# AK4493-v1_64_10.net
KiCad netlist of a schematic drawn in EAGLE
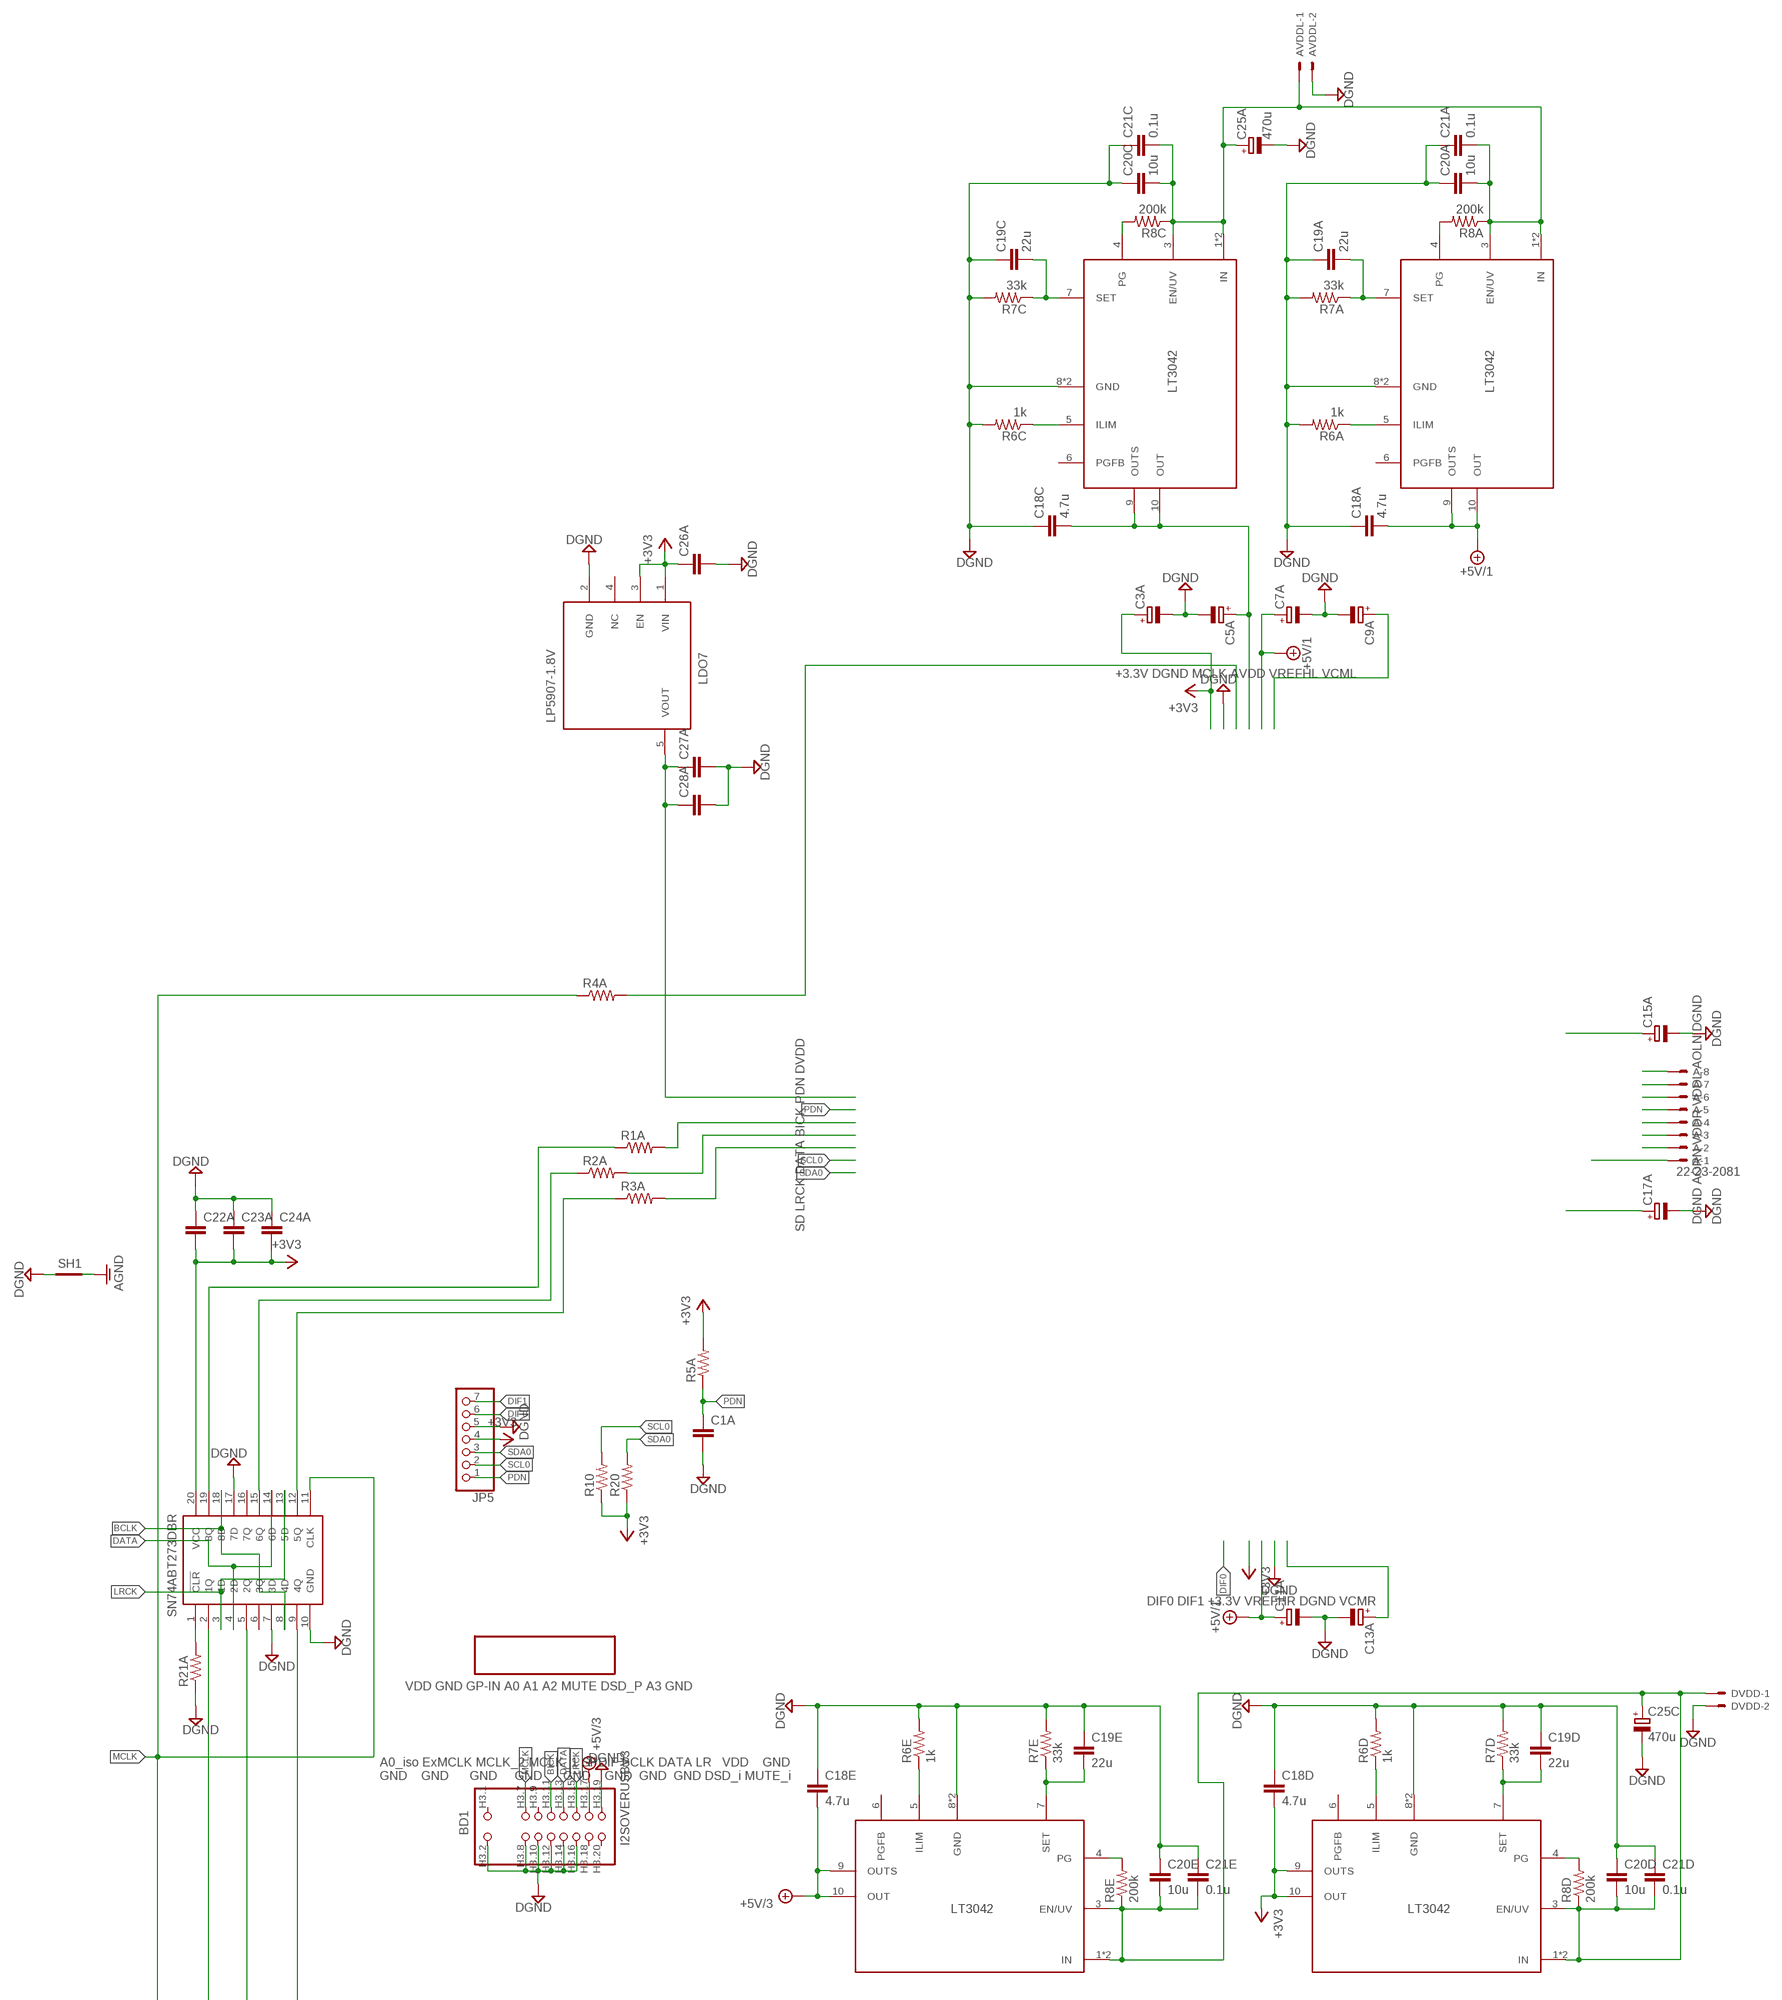
[diagram p0: schematic, sheet 1, part 1 of 2]
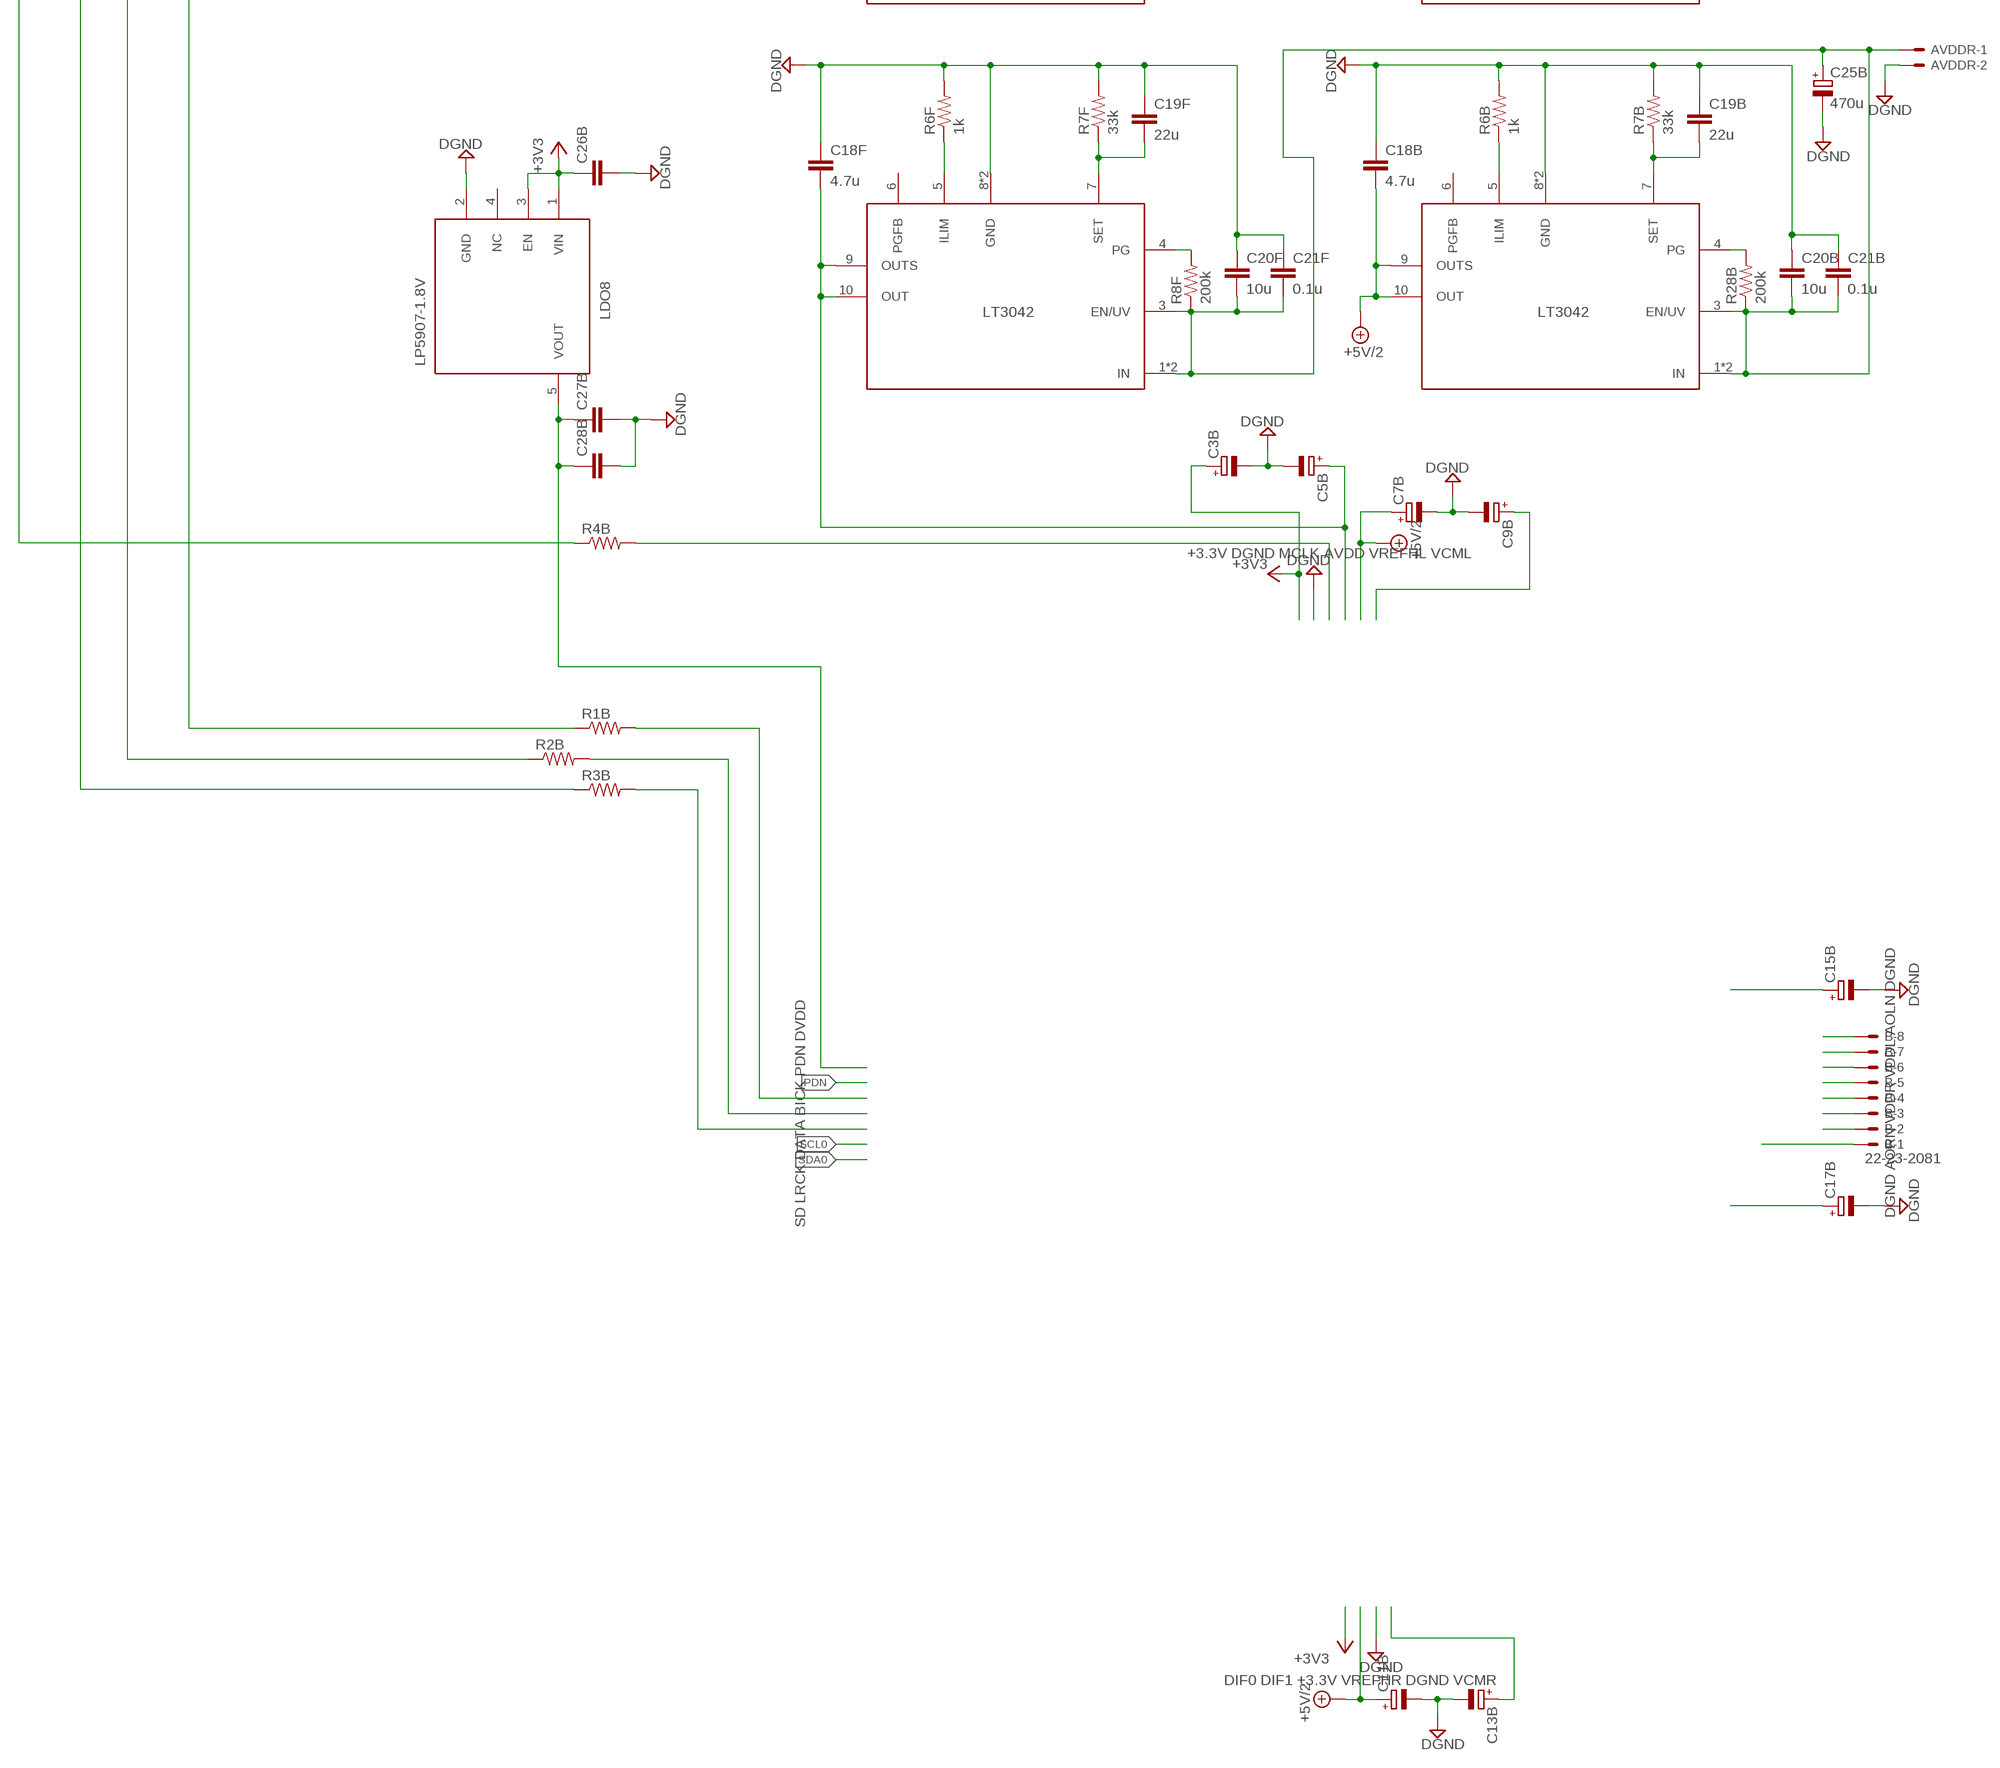
[diagram p1: schematic, sheet 1, part 2 of 2]

(export (version "E")
  (design (tool "Eeschema 10.0.6"))
  (components
    (comp (ref "A")
      (value "22-23-2081")
      (footprint "eagle-import:22-23-2081")
      (fields (field (name "MF") "MOLEX"))
      (libsource (lib "eagle-import") (part "22-23-2081"))
    )
    (comp (ref "AVDDL")
      (value "22-23-2021")
      (footprint "eagle-import:22-23-2021")
      (fields (field (name "MF") "MOLEX"))
      (libsource (lib "eagle-import") (part "22-23-2021"))
    )
    (comp (ref "AVDDR")
      (value "22-23-2021")
      (footprint "eagle-import:22-23-2021")
      (fields (field (name "MF") "MOLEX"))
      (libsource (lib "eagle-import") (part "22-23-2021"))
    )
    (comp (ref "B")
      (value "22-23-2081")
      (footprint "eagle-import:22-23-2081")
      (fields (field (name "MF") "MOLEX"))
      (libsource (lib "eagle-import") (part "22-23-2081"))
    )
    (comp (ref "BD1")
      (value "I2SOVERUSBV3")
      (footprint "eagle-import:I2SOVERUSBV3")
      (libsource (lib "eagle-import") (part "I2SOVERUSBV3"))
    )
    (comp (ref "C1A")
      (value "C-EUC0805K")
      (footprint "eagle-import:C0805K")
      (libsource (lib "eagle-import") (part "C-EUC0805K"))
    )
    (comp (ref "C3A")
      (value "CPOL-EUE2.5-5")
      (footprint "eagle-import:E2,5-5")
      (libsource (lib "eagle-import") (part "CPOL-EUE2.5-5"))
    )
    (comp (ref "C3B")
      (value "CPOL-EUE2.5-5")
      (footprint "eagle-import:E2,5-5")
      (libsource (lib "eagle-import") (part "CPOL-EUE2.5-5"))
    )
    (comp (ref "C5A")
      (value "CPOL-EUE2.5-5")
      (footprint "eagle-import:E2,5-5")
      (libsource (lib "eagle-import") (part "CPOL-EUE2.5-5"))
    )
    (comp (ref "C5B")
      (value "CPOL-EUE2.5-5")
      (footprint "eagle-import:E2,5-5")
      (libsource (lib "eagle-import") (part "CPOL-EUE2.5-5"))
    )
    (comp (ref "C7A")
      (value "CPOL-EUE5-8.5")
      (footprint "eagle-import:E5-8,5")
      (libsource (lib "eagle-import") (part "CPOL-EUE5-8.5"))
    )
    (comp (ref "C7B")
      (value "CPOL-EUE5-8.5")
      (footprint "eagle-import:E5-8,5")
      (libsource (lib "eagle-import") (part "CPOL-EUE5-8.5"))
    )
    (comp (ref "C9A")
      (value "CPOL-EUE2-4")
      (footprint "eagle-import:E2-4")
      (libsource (lib "eagle-import") (part "CPOL-EUE2-4"))
    )
    (comp (ref "C9B")
      (value "CPOL-EUE2-4")
      (footprint "eagle-import:E2-4")
      (libsource (lib "eagle-import") (part "CPOL-EUE2-4"))
    )
    (comp (ref "C11A")
      (value "CPOL-EUE5-8.5")
      (footprint "eagle-import:E5-8,5")
      (libsource (lib "eagle-import") (part "CPOL-EUE5-8.5"))
    )
    (comp (ref "C11B")
      (value "CPOL-EUE5-8.5")
      (footprint "eagle-import:E5-8,5")
      (libsource (lib "eagle-import") (part "CPOL-EUE5-8.5"))
    )
    (comp (ref "C13A")
      (value "CPOL-EUE2-4")
      (footprint "eagle-import:E2-4")
      (libsource (lib "eagle-import") (part "CPOL-EUE2-4"))
    )
    (comp (ref "C13B")
      (value "CPOL-EUE2-4")
      (footprint "eagle-import:E2-4")
      (libsource (lib "eagle-import") (part "CPOL-EUE2-4"))
    )
    (comp (ref "C15A")
      (value "CPOL-EUE2-4")
      (footprint "eagle-import:E2-4")
      (libsource (lib "eagle-import") (part "CPOL-EUE2-4"))
    )
    (comp (ref "C15B")
      (value "CPOL-EUE2-4")
      (footprint "eagle-import:E2-4")
      (libsource (lib "eagle-import") (part "CPOL-EUE2-4"))
    )
    (comp (ref "C17A")
      (value "CPOL-EUE2-4")
      (footprint "eagle-import:E2-4")
      (libsource (lib "eagle-import") (part "CPOL-EUE2-4"))
    )
    (comp (ref "C17B")
      (value "CPOL-EUE2-4")
      (footprint "eagle-import:E2-4")
      (libsource (lib "eagle-import") (part "CPOL-EUE2-4"))
    )
    (comp (ref "C18A")
      (value "4.7u")
      (footprint "eagle-import:C0805K")
      (libsource (lib "eagle-import") (part "C-EUC0805K"))
    )
    (comp (ref "C18B")
      (value "4.7u")
      (footprint "eagle-import:C0805K")
      (libsource (lib "eagle-import") (part "C-EUC0805K"))
    )
    (comp (ref "C18C")
      (value "4.7u")
      (footprint "eagle-import:C0805K")
      (libsource (lib "eagle-import") (part "C-EUC0805K"))
    )
    (comp (ref "C18D")
      (value "4.7u")
      (footprint "eagle-import:C0805K")
      (libsource (lib "eagle-import") (part "C-EUC0805K"))
    )
    (comp (ref "C18E")
      (value "4.7u")
      (footprint "eagle-import:C0805K")
      (libsource (lib "eagle-import") (part "C-EUC0805K"))
    )
    (comp (ref "C18F")
      (value "4.7u")
      (footprint "eagle-import:C0805K")
      (libsource (lib "eagle-import") (part "C-EUC0805K"))
    )
    (comp (ref "C19A")
      (value "22u")
      (footprint "eagle-import:C1206K")
      (libsource (lib "eagle-import") (part "C-EUC1206K"))
    )
    (comp (ref "C19B")
      (value "22u")
      (footprint "eagle-import:C1206K")
      (libsource (lib "eagle-import") (part "C-EUC1206K"))
    )
    (comp (ref "C19C")
      (value "22u")
      (footprint "eagle-import:C1206K")
      (libsource (lib "eagle-import") (part "C-EUC1206K"))
    )
    (comp (ref "C19D")
      (value "22u")
      (footprint "eagle-import:C1206K")
      (libsource (lib "eagle-import") (part "C-EUC1206K"))
    )
    (comp (ref "C19E")
      (value "22u")
      (footprint "eagle-import:C1206K")
      (libsource (lib "eagle-import") (part "C-EUC1206K"))
    )
    (comp (ref "C19F")
      (value "22u")
      (footprint "eagle-import:C1206K")
      (libsource (lib "eagle-import") (part "C-EUC1206K"))
    )
    (comp (ref "C20A")
      (value "10u")
      (footprint "eagle-import:C0805K")
      (libsource (lib "eagle-import") (part "C-EUC0805K"))
    )
    (comp (ref "C20B")
      (value "10u")
      (footprint "eagle-import:C0805K")
      (libsource (lib "eagle-import") (part "C-EUC0805K"))
    )
    (comp (ref "C20C")
      (value "10u")
      (footprint "eagle-import:C0805K")
      (libsource (lib "eagle-import") (part "C-EUC0805K"))
    )
    (comp (ref "C20D")
      (value "10u")
      (footprint "eagle-import:C0805K")
      (libsource (lib "eagle-import") (part "C-EUC0805K"))
    )
    (comp (ref "C20E")
      (value "10u")
      (footprint "eagle-import:C0805K")
      (libsource (lib "eagle-import") (part "C-EUC0805K"))
    )
    (comp (ref "C20F")
      (value "10u")
      (footprint "eagle-import:C0805K")
      (libsource (lib "eagle-import") (part "C-EUC0805K"))
    )
    (comp (ref "C21A")
      (value "0.1u")
      (footprint "eagle-import:C0805K")
      (libsource (lib "eagle-import") (part "C-EUC0805K"))
    )
    (comp (ref "C21B")
      (value "0.1u")
      (footprint "eagle-import:C0805K")
      (libsource (lib "eagle-import") (part "C-EUC0805K"))
    )
    (comp (ref "C21C")
      (value "0.1u")
      (footprint "eagle-import:C0805K")
      (libsource (lib "eagle-import") (part "C-EUC0805K"))
    )
    (comp (ref "C21D")
      (value "0.1u")
      (footprint "eagle-import:C0805K")
      (libsource (lib "eagle-import") (part "C-EUC0805K"))
    )
    (comp (ref "C21E")
      (value "0.1u")
      (footprint "eagle-import:C0805K")
      (libsource (lib "eagle-import") (part "C-EUC0805K"))
    )
    (comp (ref "C21F")
      (value "0.1u")
      (footprint "eagle-import:C0805K")
      (libsource (lib "eagle-import") (part "C-EUC0805K"))
    )
    (comp (ref "C22A")
      (value "C-EUC0603K")
      (footprint "eagle-import:C0603K")
      (libsource (lib "eagle-import") (part "C-EUC0603K"))
    )
    (comp (ref "C23A")
      (value "C-EUC0603K")
      (footprint "eagle-import:C0603K")
      (libsource (lib "eagle-import") (part "C-EUC0603K"))
    )
    (comp (ref "C24A")
      (value "C-EUC0603K")
      (footprint "eagle-import:C0603K")
      (libsource (lib "eagle-import") (part "C-EUC0603K"))
    )
    (comp (ref "C25A")
      (value "470u")
      (footprint "eagle-import:E2,5-7")
      (libsource (lib "eagle-import") (part "CPOL-EUE2.5-7"))
    )
    (comp (ref "C25B")
      (value "470u")
      (footprint "eagle-import:E2,5-7")
      (libsource (lib "eagle-import") (part "CPOL-EUE2.5-7"))
    )
    (comp (ref "C25C")
      (value "470u")
      (footprint "eagle-import:E2,5-7")
      (libsource (lib "eagle-import") (part "CPOL-EUE2.5-7"))
    )
    (comp (ref "C26A")
      (value "C-EUC0805K")
      (footprint "eagle-import:C0805K")
      (libsource (lib "eagle-import") (part "C-EUC0805K"))
    )
    (comp (ref "C26B")
      (value "C-EUC0805K")
      (footprint "eagle-import:C0805K")
      (libsource (lib "eagle-import") (part "C-EUC0805K"))
    )
    (comp (ref "C27A")
      (value "C-EUC0805K")
      (footprint "eagle-import:C0805K")
      (libsource (lib "eagle-import") (part "C-EUC0805K"))
    )
    (comp (ref "C27B")
      (value "C-EUC0805K")
      (footprint "eagle-import:C0805K")
      (libsource (lib "eagle-import") (part "C-EUC0805K"))
    )
    (comp (ref "C28A")
      (value "C-EUC0603K")
      (footprint "eagle-import:C0603K")
      (libsource (lib "eagle-import") (part "C-EUC0603K"))
    )
    (comp (ref "C28B")
      (value "C-EUC0603K")
      (footprint "eagle-import:C0603K")
      (libsource (lib "eagle-import") (part "C-EUC0603K"))
    )
    (comp (ref "DVDD")
      (value "22-23-2021")
      (footprint "eagle-import:22-23-2021")
      (fields (field (name "MF") "MOLEX"))
      (libsource (lib "eagle-import") (part "22-23-2021"))
    )
    (comp (ref "IC4A")
      (value "SN74ABT273DBR")
      (footprint "eagle-import:SOP65P780X200-20N")
      (fields (field (name "MOUSER_PART_NUMBER") "595-SN74ABT273DBR"))
      (libsource (lib "eagle-import") (part "SN74ABT273DBR"))
    )
    (comp (ref "JP5")
      (value "PINHD-1X7")
      (footprint "eagle-import:1X07")
      (libsource (lib "eagle-import") (part "PINHD-1X7"))
    )
    (comp (ref "LDO1")
      (value "LT3042")
      (footprint "eagle-import:SOP50P490X110-11N")
      (fields
        (field (name "MANUFACTURER_PART_NUMBER") "LT3042EMSE#PBF")
        (field (name "MOUSER_PART_NUMBER") "584-LT3042EMSE#PBF")
      )
      (libsource (lib "eagle-import") (part "LT3042"))
    )
    (comp (ref "LDO2")
      (value "LT3042")
      (footprint "eagle-import:SOP50P490X110-11N")
      (fields
        (field (name "MANUFACTURER_PART_NUMBER") "LT3042EMSE#PBF")
        (field (name "MOUSER_PART_NUMBER") "584-LT3042EMSE#PBF")
      )
      (libsource (lib "eagle-import") (part "LT3042"))
    )
    (comp (ref "LDO3")
      (value "LT3042")
      (footprint "eagle-import:SOP50P490X110-11N")
      (fields
        (field (name "MANUFACTURER_PART_NUMBER") "LT3042EMSE#PBF")
        (field (name "MOUSER_PART_NUMBER") "584-LT3042EMSE#PBF")
      )
      (libsource (lib "eagle-import") (part "LT3042"))
    )
    (comp (ref "LDO4")
      (value "LT3042")
      (footprint "eagle-import:SOP50P490X110-11N")
      (fields
        (field (name "MANUFACTURER_PART_NUMBER") "LT3042EMSE#PBF")
        (field (name "MOUSER_PART_NUMBER") "584-LT3042EMSE#PBF")
      )
      (libsource (lib "eagle-import") (part "LT3042"))
    )
    (comp (ref "LDO5")
      (value "LT3042")
      (footprint "eagle-import:SOP50P490X110-11N")
      (fields
        (field (name "MANUFACTURER_PART_NUMBER") "LT3042EMSE#PBF")
        (field (name "MOUSER_PART_NUMBER") "584-LT3042EMSE#PBF")
      )
      (libsource (lib "eagle-import") (part "LT3042"))
    )
    (comp (ref "LDO7")
      (value "LP5907-1.8V")
      (footprint "eagle-import:SOT95P280X145-5N")
      (fields
        (field (name "ARROW_PART_NUMBER") "LP5907MFX-1.8/NOPB")
        (field (name "MOUSER_PART_NUMBER") "595-LP5907MFX-1.8NPB")
      )
      (libsource (lib "eagle-import") (part "LP5907-1.8V"))
    )
    (comp (ref "LDO8")
      (value "LP5907-1.8V")
      (footprint "eagle-import:SOT95P280X145-5N")
      (fields
        (field (name "ARROW_PART_NUMBER") "LP5907MFX-1.8/NOPB")
        (field (name "MOUSER_PART_NUMBER") "595-LP5907MFX-1.8NPB")
      )
      (libsource (lib "eagle-import") (part "LP5907-1.8V"))
    )
    (comp (ref "LDO9")
      (value "LT3042")
      (footprint "eagle-import:SOP50P490X110-11N")
      (fields
        (field (name "MANUFACTURER_PART_NUMBER") "LT3042EMSE#PBF")
        (field (name "MOUSER_PART_NUMBER") "584-LT3042EMSE#PBF")
      )
      (libsource (lib "eagle-import") (part "LT3042"))
    )
    (comp (ref "R1A")
      (value "R-US_R0603")
      (footprint "eagle-import:R0603")
      (libsource (lib "eagle-import") (part "R-US_R0603"))
    )
    (comp (ref "R1B")
      (value "R-US_R0603")
      (footprint "eagle-import:R0603")
      (libsource (lib "eagle-import") (part "R-US_R0603"))
    )
    (comp (ref "R2A")
      (value "R-US_R0603")
      (footprint "eagle-import:R0603")
      (libsource (lib "eagle-import") (part "R-US_R0603"))
    )
    (comp (ref "R2B")
      (value "R-US_R0603")
      (footprint "eagle-import:R0603")
      (libsource (lib "eagle-import") (part "R-US_R0603"))
    )
    (comp (ref "R3A")
      (value "R-US_R0603")
      (footprint "eagle-import:R0603")
      (libsource (lib "eagle-import") (part "R-US_R0603"))
    )
    (comp (ref "R3B")
      (value "R-US_R0603")
      (footprint "eagle-import:R0603")
      (libsource (lib "eagle-import") (part "R-US_R0603"))
    )
    (comp (ref "R4A")
      (value "R-US_R0603")
      (footprint "eagle-import:R0603")
      (libsource (lib "eagle-import") (part "R-US_R0603"))
    )
    (comp (ref "R4B")
      (value "R-US_R0603")
      (footprint "eagle-import:R0603")
      (libsource (lib "eagle-import") (part "R-US_R0603"))
    )
    (comp (ref "R5A")
      (value "R-US_R0805")
      (footprint "eagle-import:R0805")
      (libsource (lib "eagle-import") (part "R-US_R0805"))
    )
    (comp (ref "R6A")
      (value "1k")
      (footprint "eagle-import:R0805")
      (libsource (lib "eagle-import") (part "R-US_R0805"))
    )
    (comp (ref "R6B")
      (value "1k")
      (footprint "eagle-import:R0805")
      (libsource (lib "eagle-import") (part "R-US_R0805"))
    )
    (comp (ref "R6C")
      (value "1k")
      (footprint "eagle-import:R0805")
      (libsource (lib "eagle-import") (part "R-US_R0805"))
    )
    (comp (ref "R6D")
      (value "1k")
      (footprint "eagle-import:R0805")
      (libsource (lib "eagle-import") (part "R-US_R0805"))
    )
    (comp (ref "R6E")
      (value "1k")
      (footprint "eagle-import:R0805")
      (libsource (lib "eagle-import") (part "R-US_R0805"))
    )
    (comp (ref "R6F")
      (value "1k")
      (footprint "eagle-import:R0805")
      (libsource (lib "eagle-import") (part "R-US_R0805"))
    )
    (comp (ref "R7A")
      (value "33k")
      (footprint "eagle-import:R0805")
      (libsource (lib "eagle-import") (part "R-US_R0805"))
    )
    (comp (ref "R7B")
      (value "33k")
      (footprint "eagle-import:R0805")
      (libsource (lib "eagle-import") (part "R-US_R0805"))
    )
    (comp (ref "R7C")
      (value "33k")
      (footprint "eagle-import:R0805")
      (libsource (lib "eagle-import") (part "R-US_R0805"))
    )
    (comp (ref "R7D")
      (value "33k")
      (footprint "eagle-import:R0805")
      (libsource (lib "eagle-import") (part "R-US_R0805"))
    )
    (comp (ref "R7E")
      (value "33k")
      (footprint "eagle-import:R0805")
      (libsource (lib "eagle-import") (part "R-US_R0805"))
    )
    (comp (ref "R7F")
      (value "33k")
      (footprint "eagle-import:R0805")
      (libsource (lib "eagle-import") (part "R-US_R0805"))
    )
    (comp (ref "R8A")
      (value "200k")
      (footprint "eagle-import:R0805")
      (libsource (lib "eagle-import") (part "R-US_R0805"))
    )
    (comp (ref "R8C")
      (value "200k")
      (footprint "eagle-import:R0805")
      (libsource (lib "eagle-import") (part "R-US_R0805"))
    )
    (comp (ref "R8D")
      (value "200k")
      (footprint "eagle-import:R0805")
      (libsource (lib "eagle-import") (part "R-US_R0805"))
    )
    (comp (ref "R8E")
      (value "200k")
      (footprint "eagle-import:R0805")
      (libsource (lib "eagle-import") (part "R-US_R0805"))
    )
    (comp (ref "R8F")
      (value "200k")
      (footprint "eagle-import:R0805")
      (libsource (lib "eagle-import") (part "R-US_R0805"))
    )
    (comp (ref "R10")
      (value "R-US_R0805")
      (footprint "eagle-import:R0805")
      (libsource (lib "eagle-import") (part "R-US_R0805"))
    )
    (comp (ref "R20")
      (value "R-US_R0805")
      (footprint "eagle-import:R0805")
      (libsource (lib "eagle-import") (part "R-US_R0805"))
    )
    (comp (ref "R21A")
      (value "R-US_R0805")
      (footprint "eagle-import:R0805")
      (libsource (lib "eagle-import") (part "R-US_R0805"))
    )
    (comp (ref "R28B")
      (value "200k")
      (footprint "eagle-import:R0805")
      (libsource (lib "eagle-import") (part "R-US_R0805"))
    )
    (comp (ref "SH1")
      (value "SHORTA5")
      (footprint "eagle-import:SHORT_ALL-50")
      (libsource (lib "eagle-import") (part "SHORTA5"))
    )
  )
  (nets
    (net (code "1") (name "+3V3") (class "Default")
      (node (ref "C18D") (pin "2") (pinfunction "2_2") (pintype "passive"))
      (node (ref "C22A") (pin "2") (pinfunction "2_2") (pintype "passive"))
      (node (ref "C23A") (pin "2") (pinfunction "2_2") (pintype "passive"))
      (node (ref "C24A") (pin "2") (pinfunction "2_2") (pintype "passive"))
      (node (ref "C26A") (pin "1") (pinfunction "1_1") (pintype "passive"))
      (node (ref "C26B") (pin "1") (pinfunction "1_1") (pintype "passive"))
      (node (ref "C3A") (pin "+") (pinfunction "+_+") (pintype "passive"))
      (node (ref "C3B") (pin "+") (pinfunction "+_+") (pintype "passive"))
      (node (ref "IC4A") (pin "20") (pinfunction "VCC_20") (pintype "bidirectional"))
      (node (ref "JP5") (pin "4") (pinfunction "4_4") (pintype "passive"))
      (node (ref "LDO1") (pin "10") (pinfunction "OUT_10") (pintype "bidirectional"))
      (node (ref "LDO1") (pin "9") (pinfunction "OUTS_9") (pintype "bidirectional"))
      (node (ref "LDO7") (pin "1") (pinfunction "VIN_1") (pintype "bidirectional"))
      (node (ref "LDO7") (pin "3") (pinfunction "EN_3") (pintype "bidirectional"))
      (node (ref "LDO8") (pin "1") (pinfunction "VIN_1") (pintype "bidirectional"))
      (node (ref "LDO8") (pin "3") (pinfunction "EN_3") (pintype "bidirectional"))
      (node (ref "R10") (pin "1") (pinfunction "1_1") (pintype "passive"))
      (node (ref "R20") (pin "1") (pinfunction "1_1") (pintype "passive"))
      (node (ref "R5A") (pin "2") (pinfunction "2_2") (pintype "passive"))
    )
    (net (code "2") (name "+5V{slash}1") (class "Default")
      (node (ref "C11A") (pin "+") (pinfunction "+_+") (pintype "passive"))
      (node (ref "C18A") (pin "2") (pinfunction "2_2") (pintype "passive"))
      (node (ref "C7A") (pin "+") (pinfunction "+_+") (pintype "passive"))
      (node (ref "LDO3") (pin "10") (pinfunction "OUT_10") (pintype "bidirectional"))
      (node (ref "LDO3") (pin "9") (pinfunction "OUTS_9") (pintype "bidirectional"))
    )
    (net (code "3") (name "+5V{slash}2") (class "Default")
      (node (ref "C11B") (pin "+") (pinfunction "+_+") (pintype "passive"))
      (node (ref "C18B") (pin "2") (pinfunction "2_2") (pintype "passive"))
      (node (ref "C7B") (pin "+") (pinfunction "+_+") (pintype "passive"))
      (node (ref "LDO9") (pin "10") (pinfunction "OUT_10") (pintype "bidirectional"))
      (node (ref "LDO9") (pin "9") (pinfunction "OUTS_9") (pintype "bidirectional"))
    )
    (net (code "4") (name "+5V{slash}3") (class "Default")
      (node (ref "BD1") (pin "H3.17") (pinfunction "H3.17_H3.17") (pintype "passive"))
      (node (ref "C18E") (pin "2") (pinfunction "2_2") (pintype "passive"))
      (node (ref "LDO2") (pin "10") (pinfunction "OUT_10") (pintype "bidirectional"))
      (node (ref "LDO2") (pin "9") (pinfunction "OUTS_9") (pintype "bidirectional"))
    )
    (net (code "5") (name "AGND") (class "Default")
      (node (ref "SH1") (pin "2") (pinfunction "P$2_2") (pintype "bidirectional"))
    )
    (net (code "6") (name "BCLK") (class "Default")
      (node (ref "IC4A") (pin "18") (pinfunction "8D_18") (pintype "bidirectional"))
      (node (ref "IC4A") (pin "8") (pinfunction "4D_8") (pintype "bidirectional"))
    )
    (net (code "7") (name "BICK") (class "Default")
      (node (ref "BD1") (pin "H3.11") (pinfunction "H3.11_H3.11") (pintype "passive"))
    )
    (net (code "8") (name "DATA") (class "Default")
      (node (ref "BD1") (pin "H3.13") (pinfunction "H3.13_H3.13") (pintype "passive"))
      (node (ref "IC4A") (pin "14") (pinfunction "6D_14") (pintype "bidirectional"))
      (node (ref "IC4A") (pin "4") (pinfunction "2D_4") (pintype "bidirectional"))
    )
    (net (code "9") (name "DGND") (class "Default")
      (node (ref "AVDDL") (pin "2") (pinfunction "S_2") (pintype "passive"))
      (node (ref "AVDDR") (pin "2") (pinfunction "S_2") (pintype "passive"))
      (node (ref "BD1") (pin "H3.10") (pinfunction "H3.10_H3.10") (pintype "passive"))
      (node (ref "BD1") (pin "H3.12") (pinfunction "H3.12_H3.12") (pintype "passive"))
      (node (ref "BD1") (pin "H3.14") (pinfunction "H3.14_H3.14") (pintype "passive"))
      (node (ref "BD1") (pin "H3.16") (pinfunction "H3.16_H3.16") (pintype "passive"))
      (node (ref "BD1") (pin "H3.19") (pinfunction "H3.19_H3.19") (pintype "passive"))
      (node (ref "BD1") (pin "H3.2") (pinfunction "H3.2_H3.2") (pintype "passive"))
      (node (ref "BD1") (pin "H3.8") (pinfunction "H3.8_H3.8") (pintype "passive"))
      (node (ref "C11A") (pin "-") (pinfunction "-_-") (pintype "passive"))
      (node (ref "C11B") (pin "-") (pinfunction "-_-") (pintype "passive"))
      (node (ref "C13A") (pin "-") (pinfunction "-_-") (pintype "passive"))
      (node (ref "C13B") (pin "-") (pinfunction "-_-") (pintype "passive"))
      (node (ref "C15A") (pin "-") (pinfunction "-_-") (pintype "passive"))
      (node (ref "C15B") (pin "-") (pinfunction "-_-") (pintype "passive"))
      (node (ref "C17A") (pin "-") (pinfunction "-_-") (pintype "passive"))
      (node (ref "C17B") (pin "-") (pinfunction "-_-") (pintype "passive"))
      (node (ref "C18A") (pin "1") (pinfunction "1_1") (pintype "passive"))
      (node (ref "C18B") (pin "1") (pinfunction "1_1") (pintype "passive"))
      (node (ref "C18C") (pin "1") (pinfunction "1_1") (pintype "passive"))
      (node (ref "C18D") (pin "1") (pinfunction "1_1") (pintype "passive"))
      (node (ref "C18E") (pin "1") (pinfunction "1_1") (pintype "passive"))
      (node (ref "C18F") (pin "1") (pinfunction "1_1") (pintype "passive"))
      (node (ref "C19A") (pin "1") (pinfunction "1_1") (pintype "passive"))
      (node (ref "C19B") (pin "1") (pinfunction "1_1") (pintype "passive"))
      (node (ref "C19C") (pin "1") (pinfunction "1_1") (pintype "passive"))
      (node (ref "C19D") (pin "1") (pinfunction "1_1") (pintype "passive"))
      (node (ref "C19E") (pin "1") (pinfunction "1_1") (pintype "passive"))
      (node (ref "C19F") (pin "1") (pinfunction "1_1") (pintype "passive"))
      (node (ref "C1A") (pin "2") (pinfunction "2_2") (pintype "passive"))
      (node (ref "C20A") (pin "1") (pinfunction "1_1") (pintype "passive"))
      (node (ref "C20B") (pin "1") (pinfunction "1_1") (pintype "passive"))
      (node (ref "C20C") (pin "1") (pinfunction "1_1") (pintype "passive"))
      (node (ref "C20D") (pin "1") (pinfunction "1_1") (pintype "passive"))
      (node (ref "C20E") (pin "1") (pinfunction "1_1") (pintype "passive"))
      (node (ref "C20F") (pin "1") (pinfunction "1_1") (pintype "passive"))
      (node (ref "C21A") (pin "1") (pinfunction "1_1") (pintype "passive"))
      (node (ref "C21B") (pin "1") (pinfunction "1_1") (pintype "passive"))
      (node (ref "C21C") (pin "1") (pinfunction "1_1") (pintype "passive"))
      (node (ref "C21D") (pin "1") (pinfunction "1_1") (pintype "passive"))
      (node (ref "C21E") (pin "1") (pinfunction "1_1") (pintype "passive"))
      (node (ref "C21F") (pin "1") (pinfunction "1_1") (pintype "passive"))
      (node (ref "C22A") (pin "1") (pinfunction "1_1") (pintype "passive"))
      (node (ref "C23A") (pin "1") (pinfunction "1_1") (pintype "passive"))
      (node (ref "C24A") (pin "1") (pinfunction "1_1") (pintype "passive"))
      (node (ref "C25A") (pin "-") (pinfunction "-_-") (pintype "passive"))
      (node (ref "C25B") (pin "-") (pinfunction "-_-") (pintype "passive"))
      (node (ref "C25C") (pin "-") (pinfunction "-_-") (pintype "passive"))
      (node (ref "C26A") (pin "2") (pinfunction "2_2") (pintype "passive"))
      (node (ref "C26B") (pin "2") (pinfunction "2_2") (pintype "passive"))
      (node (ref "C27A") (pin "2") (pinfunction "2_2") (pintype "passive"))
      (node (ref "C27B") (pin "2") (pinfunction "2_2") (pintype "passive"))
      (node (ref "C28A") (pin "2") (pinfunction "2_2") (pintype "passive"))
      (node (ref "C28B") (pin "2") (pinfunction "2_2") (pintype "passive"))
      (node (ref "C3A") (pin "-") (pinfunction "-_-") (pintype "passive"))
      (node (ref "C3B") (pin "-") (pinfunction "-_-") (pintype "passive"))
      (node (ref "C5A") (pin "-") (pinfunction "-_-") (pintype "passive"))
      (node (ref "C5B") (pin "-") (pinfunction "-_-") (pintype "passive"))
      (node (ref "C7A") (pin "-") (pinfunction "-_-") (pintype "passive"))
      (node (ref "C7B") (pin "-") (pinfunction "-_-") (pintype "passive"))
      (node (ref "C9A") (pin "-") (pinfunction "-_-") (pintype "passive"))
      (node (ref "C9B") (pin "-") (pinfunction "-_-") (pintype "passive"))
      (node (ref "DVDD") (pin "2") (pinfunction "S_2") (pintype "passive"))
      (node (ref "IC4A") (pin "10") (pinfunction "GND_10") (pintype "bidirectional"))
      (node (ref "IC4A") (pin "17") (pinfunction "7D_17") (pintype "bidirectional"))
      (node (ref "IC4A") (pin "7") (pinfunction "3D_7") (pintype "bidirectional"))
      (node (ref "JP5") (pin "5") (pinfunction "5_5") (pintype "passive"))
      (node (ref "LDO1") (pin "11") (pinfunction "GND_11") (pintype "bidirectional"))
      (node (ref "LDO1") (pin "8") (pinfunction "GND_8") (pintype "bidirectional"))
      (node (ref "LDO2") (pin "11") (pinfunction "GND_11") (pintype "bidirectional"))
      (node (ref "LDO2") (pin "8") (pinfunction "GND_8") (pintype "bidirectional"))
      (node (ref "LDO3") (pin "11") (pinfunction "GND_11") (pintype "bidirectional"))
      (node (ref "LDO3") (pin "8") (pinfunction "GND_8") (pintype "bidirectional"))
      (node (ref "LDO4") (pin "11") (pinfunction "GND_11") (pintype "bidirectional"))
      (node (ref "LDO4") (pin "8") (pinfunction "GND_8") (pintype "bidirectional"))
      (node (ref "LDO5") (pin "11") (pinfunction "GND_11") (pintype "bidirectional"))
      (node (ref "LDO5") (pin "8") (pinfunction "GND_8") (pintype "bidirectional"))
      (node (ref "LDO7") (pin "2") (pinfunction "GND_2") (pintype "bidirectional"))
      (node (ref "LDO8") (pin "2") (pinfunction "GND_2") (pintype "bidirectional"))
      (node (ref "LDO9") (pin "11") (pinfunction "GND_11") (pintype "bidirectional"))
      (node (ref "LDO9") (pin "8") (pinfunction "GND_8") (pintype "bidirectional"))
      (node (ref "R21A") (pin "1") (pinfunction "1_1") (pintype "passive"))
      (node (ref "R6A") (pin "2") (pinfunction "2_2") (pintype "passive"))
      (node (ref "R6B") (pin "2") (pinfunction "2_2") (pintype "passive"))
      (node (ref "R6C") (pin "2") (pinfunction "2_2") (pintype "passive"))
      (node (ref "R6D") (pin "2") (pinfunction "2_2") (pintype "passive"))
      (node (ref "R6E") (pin "2") (pinfunction "2_2") (pintype "passive"))
      (node (ref "R6F") (pin "2") (pinfunction "2_2") (pintype "passive"))
      (node (ref "R7A") (pin "2") (pinfunction "2_2") (pintype "passive"))
      (node (ref "R7B") (pin "2") (pinfunction "2_2") (pintype "passive"))
      (node (ref "R7C") (pin "2") (pinfunction "2_2") (pintype "passive"))
      (node (ref "R7D") (pin "2") (pinfunction "2_2") (pintype "passive"))
      (node (ref "R7E") (pin "2") (pinfunction "2_2") (pintype "passive"))
      (node (ref "R7F") (pin "2") (pinfunction "2_2") (pintype "passive"))
      (node (ref "SH1") (pin "1") (pinfunction "P$1_1") (pintype "bidirectional"))
    )
    (net (code "10") (name "DIF0") (class "Default")
      (node (ref "JP5") (pin "6") (pinfunction "6_6") (pintype "passive"))
    )
    (net (code "11") (name "DIF1") (class "Default")
      (node (ref "JP5") (pin "7") (pinfunction "7_7") (pintype "passive"))
    )
    (net (code "12") (name "LRCK") (class "Default")
      (node (ref "BD1") (pin "H3.15") (pinfunction "H3.15_H3.15") (pintype "passive"))
      (node (ref "IC4A") (pin "13") (pinfunction "5D_13") (pintype "bidirectional"))
      (node (ref "IC4A") (pin "3") (pinfunction "1D_3") (pintype "bidirectional"))
    )
    (net (code "13") (name "MCLK") (class "Default")
      (node (ref "BD1") (pin "H3.7") (pinfunction "H3.7_H3.7") (pintype "passive"))
      (node (ref "IC4A") (pin "11") (pinfunction "CLK_11") (pintype "bidirectional"))
      (node (ref "R4A") (pin "1") (pinfunction "1_1") (pintype "passive"))
      (node (ref "R4B") (pin "1") (pinfunction "1_1") (pintype "passive"))
    )
    (net (code "14") (name "Net-(AVDDLA-S)") (class "Default")
      (node (ref "AVDDL") (pin "1") (pinfunction "S_1") (pintype "passive"))
      (node (ref "C20A") (pin "2") (pinfunction "2_2") (pintype "passive"))
      (node (ref "C20C") (pin "2") (pinfunction "2_2") (pintype "passive"))
      (node (ref "C21A") (pin "2") (pinfunction "2_2") (pintype "passive"))
      (node (ref "C21C") (pin "2") (pinfunction "2_2") (pintype "passive"))
      (node (ref "C25A") (pin "+") (pinfunction "+_+") (pintype "passive"))
      (node (ref "LDO3") (pin "1") (pinfunction "IN_1") (pintype "bidirectional"))
      (node (ref "LDO3") (pin "2") (pinfunction "IN_2") (pintype "bidirectional"))
      (node (ref "LDO3") (pin "3") (pinfunction "EN/UV_3") (pintype "bidirectional"))
      (node (ref "LDO5") (pin "1") (pinfunction "IN_1") (pintype "bidirectional"))
      (node (ref "LDO5") (pin "2") (pinfunction "IN_2") (pintype "bidirectional"))
      (node (ref "LDO5") (pin "3") (pinfunction "EN/UV_3") (pintype "bidirectional"))
      (node (ref "R8A") (pin "1") (pinfunction "1_1") (pintype "passive"))
      (node (ref "R8C") (pin "1") (pinfunction "1_1") (pintype "passive"))
    )
    (net (code "15") (name "Net-(AVDDRA-S)") (class "Default")
      (node (ref "AVDDR") (pin "1") (pinfunction "S_1") (pintype "passive"))
      (node (ref "C20B") (pin "2") (pinfunction "2_2") (pintype "passive"))
      (node (ref "C20F") (pin "2") (pinfunction "2_2") (pintype "passive"))
      (node (ref "C21B") (pin "2") (pinfunction "2_2") (pintype "passive"))
      (node (ref "C21F") (pin "2") (pinfunction "2_2") (pintype "passive"))
      (node (ref "C25B") (pin "+") (pinfunction "+_+") (pintype "passive"))
      (node (ref "LDO4") (pin "1") (pinfunction "IN_1") (pintype "bidirectional"))
      (node (ref "LDO4") (pin "2") (pinfunction "IN_2") (pintype "bidirectional"))
      (node (ref "LDO4") (pin "3") (pinfunction "EN/UV_3") (pintype "bidirectional"))
      (node (ref "LDO9") (pin "1") (pinfunction "IN_1") (pintype "bidirectional"))
      (node (ref "LDO9") (pin "2") (pinfunction "IN_2") (pintype "bidirectional"))
      (node (ref "LDO9") (pin "3") (pinfunction "EN/UV_3") (pintype "bidirectional"))
      (node (ref "R28B") (pin "1") (pinfunction "1_1") (pintype "passive"))
      (node (ref "R8F") (pin "1") (pinfunction "1_1") (pintype "passive"))
    )
    (net (code "16") (name "Net-(DVDDA-S)") (class "Default")
      (node (ref "C20D") (pin "2") (pinfunction "2_2") (pintype "passive"))
      (node (ref "C20E") (pin "2") (pinfunction "2_2") (pintype "passive"))
      (node (ref "C21D") (pin "2") (pinfunction "2_2") (pintype "passive"))
      (node (ref "C21E") (pin "2") (pinfunction "2_2") (pintype "passive"))
      (node (ref "C25C") (pin "+") (pinfunction "+_+") (pintype "passive"))
      (node (ref "DVDD") (pin "1") (pinfunction "S_1") (pintype "passive"))
      (node (ref "LDO1") (pin "1") (pinfunction "IN_1") (pintype "bidirectional"))
      (node (ref "LDO1") (pin "2") (pinfunction "IN_2") (pintype "bidirectional"))
      (node (ref "LDO1") (pin "3") (pinfunction "EN/UV_3") (pintype "bidirectional"))
      (node (ref "LDO2") (pin "1") (pinfunction "IN_1") (pintype "bidirectional"))
      (node (ref "LDO2") (pin "2") (pinfunction "IN_2") (pintype "bidirectional"))
      (node (ref "LDO2") (pin "3") (pinfunction "EN/UV_3") (pintype "bidirectional"))
      (node (ref "R8D") (pin "1") (pinfunction "1_1") (pintype "passive"))
      (node (ref "R8E") (pin "1") (pinfunction "1_1") (pintype "passive"))
    )
    (net (code "17") (name "Net-(IC4A-1Q)") (class "Default")
      (node (ref "IC4A") (pin "2") (pinfunction "1Q_2") (pintype "bidirectional"))
      (node (ref "R3B") (pin "1") (pinfunction "1_1") (pintype "passive"))
    )
    (net (code "18") (name "Net-(IC4A-2Q)") (class "Default")
      (node (ref "IC4A") (pin "5") (pinfunction "2Q_5") (pintype "bidirectional"))
      (node (ref "R2B") (pin "1") (pinfunction "1_1") (pintype "passive"))
    )
    (net (code "19") (name "Net-(IC4A-4Q)") (class "Default")
      (node (ref "IC4A") (pin "9") (pinfunction "4Q_9") (pintype "bidirectional"))
      (node (ref "R1B") (pin "1") (pinfunction "1_1") (pintype "passive"))
    )
    (net (code "20") (name "Net-(IC4A-5Q)") (class "Default")
      (node (ref "IC4A") (pin "12") (pinfunction "5Q_12") (pintype "bidirectional"))
      (node (ref "R3A") (pin "1") (pinfunction "1_1") (pintype "passive"))
    )
    (net (code "21") (name "Net-(IC4A-6Q)") (class "Default")
      (node (ref "IC4A") (pin "15") (pinfunction "6Q_15") (pintype "bidirectional"))
      (node (ref "R2A") (pin "1") (pinfunction "1_1") (pintype "passive"))
    )
    (net (code "22") (name "Net-(IC4A-8Q)") (class "Default")
      (node (ref "IC4A") (pin "19") (pinfunction "8Q_19") (pintype "bidirectional"))
      (node (ref "R1A") (pin "1") (pinfunction "1_1") (pintype "passive"))
    )
    (net (code "23") (name "Net-(IC4A-~{CLR})") (class "Default")
      (node (ref "IC4A") (pin "1") (pinfunction "~{CLR}_1") (pintype "bidirectional"))
      (node (ref "R21A") (pin "2") (pinfunction "2_2") (pintype "passive"))
    )
    (net (code "24") (name "Net-(LDO1-ILIM)") (class "Default")
      (node (ref "LDO1") (pin "5") (pinfunction "ILIM_5") (pintype "bidirectional"))
      (node (ref "R6D") (pin "1") (pinfunction "1_1") (pintype "passive"))
    )
    (net (code "25") (name "Net-(LDO1-PG)") (class "Default")
      (node (ref "LDO1") (pin "4") (pinfunction "PG_4") (pintype "bidirectional"))
      (node (ref "R8D") (pin "2") (pinfunction "2_2") (pintype "passive"))
    )
    (net (code "26") (name "Net-(LDO1-SET)") (class "Default")
      (node (ref "C19D") (pin "2") (pinfunction "2_2") (pintype "passive"))
      (node (ref "LDO1") (pin "7") (pinfunction "SET_7") (pintype "bidirectional"))
      (node (ref "R7D") (pin "1") (pinfunction "1_1") (pintype "passive"))
    )
    (net (code "27") (name "Net-(LDO2-ILIM)") (class "Default")
      (node (ref "LDO2") (pin "5") (pinfunction "ILIM_5") (pintype "bidirectional"))
      (node (ref "R6E") (pin "1") (pinfunction "1_1") (pintype "passive"))
    )
    (net (code "28") (name "Net-(LDO2-PG)") (class "Default")
      (node (ref "LDO2") (pin "4") (pinfunction "PG_4") (pintype "bidirectional"))
      (node (ref "R8E") (pin "2") (pinfunction "2_2") (pintype "passive"))
    )
    (net (code "29") (name "Net-(LDO2-SET)") (class "Default")
      (node (ref "C19E") (pin "2") (pinfunction "2_2") (pintype "passive"))
      (node (ref "LDO2") (pin "7") (pinfunction "SET_7") (pintype "bidirectional"))
      (node (ref "R7E") (pin "1") (pinfunction "1_1") (pintype "passive"))
    )
    (net (code "30") (name "Net-(LDO3-ILIM)") (class "Default")
      (node (ref "LDO3") (pin "5") (pinfunction "ILIM_5") (pintype "bidirectional"))
      (node (ref "R6A") (pin "1") (pinfunction "1_1") (pintype "passive"))
    )
    (net (code "31") (name "Net-(LDO3-PG)") (class "Default")
      (node (ref "LDO3") (pin "4") (pinfunction "PG_4") (pintype "bidirectional"))
      (node (ref "R8A") (pin "2") (pinfunction "2_2") (pintype "passive"))
    )
    (net (code "32") (name "Net-(LDO3-SET)") (class "Default")
      (node (ref "C19A") (pin "2") (pinfunction "2_2") (pintype "passive"))
      (node (ref "LDO3") (pin "7") (pinfunction "SET_7") (pintype "bidirectional"))
      (node (ref "R7A") (pin "1") (pinfunction "1_1") (pintype "passive"))
    )
    (net (code "33") (name "Net-(LDO4-ILIM)") (class "Default")
      (node (ref "LDO4") (pin "5") (pinfunction "ILIM_5") (pintype "bidirectional"))
      (node (ref "R6F") (pin "1") (pinfunction "1_1") (pintype "passive"))
    )
    (net (code "34") (name "Net-(LDO4-OUT)") (class "Default")
      (node (ref "C18F") (pin "2") (pinfunction "2_2") (pintype "passive"))
      (node (ref "C5B") (pin "+") (pinfunction "+_+") (pintype "passive"))
      (node (ref "LDO4") (pin "10") (pinfunction "OUT_10") (pintype "bidirectional"))
      (node (ref "LDO4") (pin "9") (pinfunction "OUTS_9") (pintype "bidirectional"))
    )
    (net (code "35") (name "Net-(LDO4-PG)") (class "Default")
      (node (ref "LDO4") (pin "4") (pinfunction "PG_4") (pintype "bidirectional"))
      (node (ref "R8F") (pin "2") (pinfunction "2_2") (pintype "passive"))
    )
    (net (code "36") (name "Net-(LDO4-SET)") (class "Default")
      (node (ref "C19F") (pin "2") (pinfunction "2_2") (pintype "passive"))
      (node (ref "LDO4") (pin "7") (pinfunction "SET_7") (pintype "bidirectional"))
      (node (ref "R7F") (pin "1") (pinfunction "1_1") (pintype "passive"))
    )
    (net (code "37") (name "Net-(LDO5-ILIM)") (class "Default")
      (node (ref "LDO5") (pin "5") (pinfunction "ILIM_5") (pintype "bidirectional"))
      (node (ref "R6C") (pin "1") (pinfunction "1_1") (pintype "passive"))
    )
    (net (code "38") (name "Net-(LDO5-OUT)") (class "Default")
      (node (ref "C18C") (pin "2") (pinfunction "2_2") (pintype "passive"))
      (node (ref "C5A") (pin "+") (pinfunction "+_+") (pintype "passive"))
      (node (ref "LDO5") (pin "10") (pinfunction "OUT_10") (pintype "bidirectional"))
      (node (ref "LDO5") (pin "9") (pinfunction "OUTS_9") (pintype "bidirectional"))
    )
    (net (code "39") (name "Net-(LDO5-PG)") (class "Default")
      (node (ref "LDO5") (pin "4") (pinfunction "PG_4") (pintype "bidirectional"))
      (node (ref "R8C") (pin "2") (pinfunction "2_2") (pintype "passive"))
    )
    (net (code "40") (name "Net-(LDO5-SET)") (class "Default")
      (node (ref "C19C") (pin "2") (pinfunction "2_2") (pintype "passive"))
      (node (ref "LDO5") (pin "7") (pinfunction "SET_7") (pintype "bidirectional"))
      (node (ref "R7C") (pin "1") (pinfunction "1_1") (pintype "passive"))
    )
    (net (code "41") (name "Net-(LDO7-VOUT)") (class "Default")
      (node (ref "C27A") (pin "1") (pinfunction "1_1") (pintype "passive"))
      (node (ref "C28A") (pin "1") (pinfunction "1_1") (pintype "passive"))
      (node (ref "LDO7") (pin "5") (pinfunction "VOUT_5") (pintype "bidirectional"))
    )
    (net (code "42") (name "Net-(LDO8-VOUT)") (class "Default")
      (node (ref "C27B") (pin "1") (pinfunction "1_1") (pintype "passive"))
      (node (ref "C28B") (pin "1") (pinfunction "1_1") (pintype "passive"))
      (node (ref "LDO8") (pin "5") (pinfunction "VOUT_5") (pintype "bidirectional"))
    )
    (net (code "43") (name "Net-(LDO9-ILIM)") (class "Default")
      (node (ref "LDO9") (pin "5") (pinfunction "ILIM_5") (pintype "bidirectional"))
      (node (ref "R6B") (pin "1") (pinfunction "1_1") (pintype "passive"))
    )
    (net (code "44") (name "Net-(LDO9-PG)") (class "Default")
      (node (ref "LDO9") (pin "4") (pinfunction "PG_4") (pintype "bidirectional"))
      (node (ref "R28B") (pin "2") (pinfunction "2_2") (pintype "passive"))
    )
    (net (code "45") (name "Net-(LDO9-SET)") (class "Default")
      (node (ref "C19B") (pin "2") (pinfunction "2_2") (pintype "passive"))
      (node (ref "LDO9") (pin "7") (pinfunction "SET_7") (pintype "bidirectional"))
      (node (ref "R7B") (pin "1") (pinfunction "1_1") (pintype "passive"))
    )
    (net (code "46") (name "PDN") (class "Default")
      (node (ref "C1A") (pin "1") (pinfunction "1_1") (pintype "passive"))
      (node (ref "JP5") (pin "1") (pinfunction "1_1") (pintype "passive"))
      (node (ref "R5A") (pin "1") (pinfunction "1_1") (pintype "passive"))
    )
    (net (code "47") (name "SCL0") (class "Default")
      (node (ref "JP5") (pin "2") (pinfunction "2_2") (pintype "passive"))
      (node (ref "R10") (pin "2") (pinfunction "2_2") (pintype "passive"))
    )
    (net (code "48") (name "SDA0") (class "Default")
      (node (ref "JP5") (pin "3") (pinfunction "3_3") (pintype "passive"))
      (node (ref "R20") (pin "2") (pinfunction "2_2") (pintype "passive"))
    )
    (net (code "49") (name "unconnected-(AA-S-Pad1)") (class "Default")
      (node (ref "A") (pin "1") (pinfunction "S_1") (pintype "passive"))
    )
    (net (code "50") (name "unconnected-(AB-S-Pad2)") (class "Default")
      (node (ref "A") (pin "2") (pinfunction "S_2") (pintype "passive"))
    )
    (net (code "51") (name "unconnected-(AC-S-Pad3)") (class "Default")
      (node (ref "A") (pin "3") (pinfunction "S_3") (pintype "passive"))
    )
    (net (code "52") (name "unconnected-(AD-S-Pad4)") (class "Default")
      (node (ref "A") (pin "4") (pinfunction "S_4") (pintype "passive"))
    )
    (net (code "53") (name "unconnected-(AE-S-Pad5)") (class "Default")
      (node (ref "A") (pin "5") (pinfunction "S_5") (pintype "passive"))
    )
    (net (code "54") (name "unconnected-(AF-S-Pad6)") (class "Default")
      (node (ref "A") (pin "6") (pinfunction "S_6") (pintype "passive"))
    )
    (net (code "55") (name "unconnected-(AG-S-Pad7)") (class "Default")
      (node (ref "A") (pin "7") (pinfunction "S_7") (pintype "passive"))
    )
    (net (code "56") (name "unconnected-(AH-S-Pad8)") (class "Default")
      (node (ref "A") (pin "8") (pinfunction "S_8") (pintype "passive"))
    )
    (net (code "57") (name "unconnected-(BA-S-Pad1)") (class "Default")
      (node (ref "B") (pin "1") (pinfunction "S_1") (pintype "passive"))
    )
    (net (code "58") (name "unconnected-(BB-S-Pad2)") (class "Default")
      (node (ref "B") (pin "2") (pinfunction "S_2") (pintype "passive"))
    )
    (net (code "59") (name "unconnected-(BC-S-Pad3)") (class "Default")
      (node (ref "B") (pin "3") (pinfunction "S_3") (pintype "passive"))
    )
    (net (code "60") (name "unconnected-(BD-S-Pad4)") (class "Default")
      (node (ref "B") (pin "4") (pinfunction "S_4") (pintype "passive"))
    )
    (net (code "61") (name "unconnected-(BD1-PadH3.1)") (class "Default")
      (node (ref "BD1") (pin "H3.1") (pinfunction "H3.1_H3.1") (pintype "passive"))
    )
    (net (code "62") (name "unconnected-(BD1-PadH3.9)") (class "Default")
      (node (ref "BD1") (pin "H3.9") (pinfunction "H3.9_H3.9") (pintype "passive"))
    )
    (net (code "63") (name "unconnected-(BD1-PadH3.18)") (class "Default")
      (node (ref "BD1") (pin "H3.18") (pinfunction "H3.18_H3.18") (pintype "passive"))
    )
    (net (code "64") (name "unconnected-(BD1-PadH3.20)") (class "Default")
      (node (ref "BD1") (pin "H3.20") (pinfunction "H3.20_H3.20") (pintype "passive"))
    )
    (net (code "65") (name "unconnected-(BE-S-Pad5)") (class "Default")
      (node (ref "B") (pin "5") (pinfunction "S_5") (pintype "passive"))
    )
    (net (code "66") (name "unconnected-(BF-S-Pad6)") (class "Default")
      (node (ref "B") (pin "6") (pinfunction "S_6") (pintype "passive"))
    )
    (net (code "67") (name "unconnected-(BG-S-Pad7)") (class "Default")
      (node (ref "B") (pin "7") (pinfunction "S_7") (pintype "passive"))
    )
    (net (code "68") (name "unconnected-(BH-S-Pad8)") (class "Default")
      (node (ref "B") (pin "8") (pinfunction "S_8") (pintype "passive"))
    )
    (net (code "69") (name "unconnected-(C9A-Pad+)") (class "Default")
      (node (ref "C9A") (pin "+") (pinfunction "+_+") (pintype "passive"))
    )
    (net (code "70") (name "unconnected-(C9B-Pad+)") (class "Default")
      (node (ref "C9B") (pin "+") (pinfunction "+_+") (pintype "passive"))
    )
    (net (code "71") (name "unconnected-(C13A-Pad+)") (class "Default")
      (node (ref "C13A") (pin "+") (pinfunction "+_+") (pintype "passive"))
    )
    (net (code "72") (name "unconnected-(C13B-Pad+)") (class "Default")
      (node (ref "C13B") (pin "+") (pinfunction "+_+") (pintype "passive"))
    )
    (net (code "73") (name "unconnected-(C15A-Pad+)") (class "Default")
      (node (ref "C15A") (pin "+") (pinfunction "+_+") (pintype "passive"))
    )
    (net (code "74") (name "unconnected-(C15B-Pad+)") (class "Default")
      (node (ref "C15B") (pin "+") (pinfunction "+_+") (pintype "passive"))
    )
    (net (code "75") (name "unconnected-(C17A-Pad+)") (class "Default")
      (node (ref "C17A") (pin "+") (pinfunction "+_+") (pintype "passive"))
    )
    (net (code "76") (name "unconnected-(C17B-Pad+)") (class "Default")
      (node (ref "C17B") (pin "+") (pinfunction "+_+") (pintype "passive"))
    )
    (net (code "77") (name "unconnected-(IC4A-3Q-Pad6)") (class "Default")
      (node (ref "IC4A") (pin "6") (pinfunction "3Q_6") (pintype "bidirectional"))
    )
    (net (code "78") (name "unconnected-(IC4A-7Q-Pad16)") (class "Default")
      (node (ref "IC4A") (pin "16") (pinfunction "7Q_16") (pintype "bidirectional"))
    )
    (net (code "79") (name "unconnected-(LDO1-PGFB-Pad6)") (class "Default")
      (node (ref "LDO1") (pin "6") (pinfunction "PGFB_6") (pintype "bidirectional"))
    )
    (net (code "80") (name "unconnected-(LDO2-PGFB-Pad6)") (class "Default")
      (node (ref "LDO2") (pin "6") (pinfunction "PGFB_6") (pintype "bidirectional"))
    )
    (net (code "81") (name "unconnected-(LDO3-PGFB-Pad6)") (class "Default")
      (node (ref "LDO3") (pin "6") (pinfunction "PGFB_6") (pintype "bidirectional"))
    )
    (net (code "82") (name "unconnected-(LDO4-PGFB-Pad6)") (class "Default")
      (node (ref "LDO4") (pin "6") (pinfunction "PGFB_6") (pintype "bidirectional"))
    )
    (net (code "83") (name "unconnected-(LDO5-PGFB-Pad6)") (class "Default")
      (node (ref "LDO5") (pin "6") (pinfunction "PGFB_6") (pintype "bidirectional"))
    )
    (net (code "84") (name "unconnected-(LDO7-NC-Pad4)") (class "Default")
      (node (ref "LDO7") (pin "4") (pinfunction "NC_4") (pintype "no_connect"))
    )
    (net (code "85") (name "unconnected-(LDO8-NC-Pad4)") (class "Default")
      (node (ref "LDO8") (pin "4") (pinfunction "NC_4") (pintype "no_connect"))
    )
    (net (code "86") (name "unconnected-(LDO9-PGFB-Pad6)") (class "Default")
      (node (ref "LDO9") (pin "6") (pinfunction "PGFB_6") (pintype "bidirectional"))
    )
    (net (code "87") (name "unconnected-(R1A-Pad2)") (class "Default")
      (node (ref "R1A") (pin "2") (pinfunction "2_2") (pintype "passive"))
    )
    (net (code "88") (name "unconnected-(R1B-Pad2)") (class "Default")
      (node (ref "R1B") (pin "2") (pinfunction "2_2") (pintype "passive"))
    )
    (net (code "89") (name "unconnected-(R2A-Pad2)") (class "Default")
      (node (ref "R2A") (pin "2") (pinfunction "2_2") (pintype "passive"))
    )
    (net (code "90") (name "unconnected-(R2B-Pad2)") (class "Default")
      (node (ref "R2B") (pin "2") (pinfunction "2_2") (pintype "passive"))
    )
    (net (code "91") (name "unconnected-(R3A-Pad2)") (class "Default")
      (node (ref "R3A") (pin "2") (pinfunction "2_2") (pintype "passive"))
    )
    (net (code "92") (name "unconnected-(R3B-Pad2)") (class "Default")
      (node (ref "R3B") (pin "2") (pinfunction "2_2") (pintype "passive"))
    )
    (net (code "93") (name "unconnected-(R4A-Pad2)") (class "Default")
      (node (ref "R4A") (pin "2") (pinfunction "2_2") (pintype "passive"))
    )
    (net (code "94") (name "unconnected-(R4B-Pad2)") (class "Default")
      (node (ref "R4B") (pin "2") (pinfunction "2_2") (pintype "passive"))
    )
  )
)
